# PCB-DISP128x32.net
KiCad netlist of a schematic drawn in EAGLE
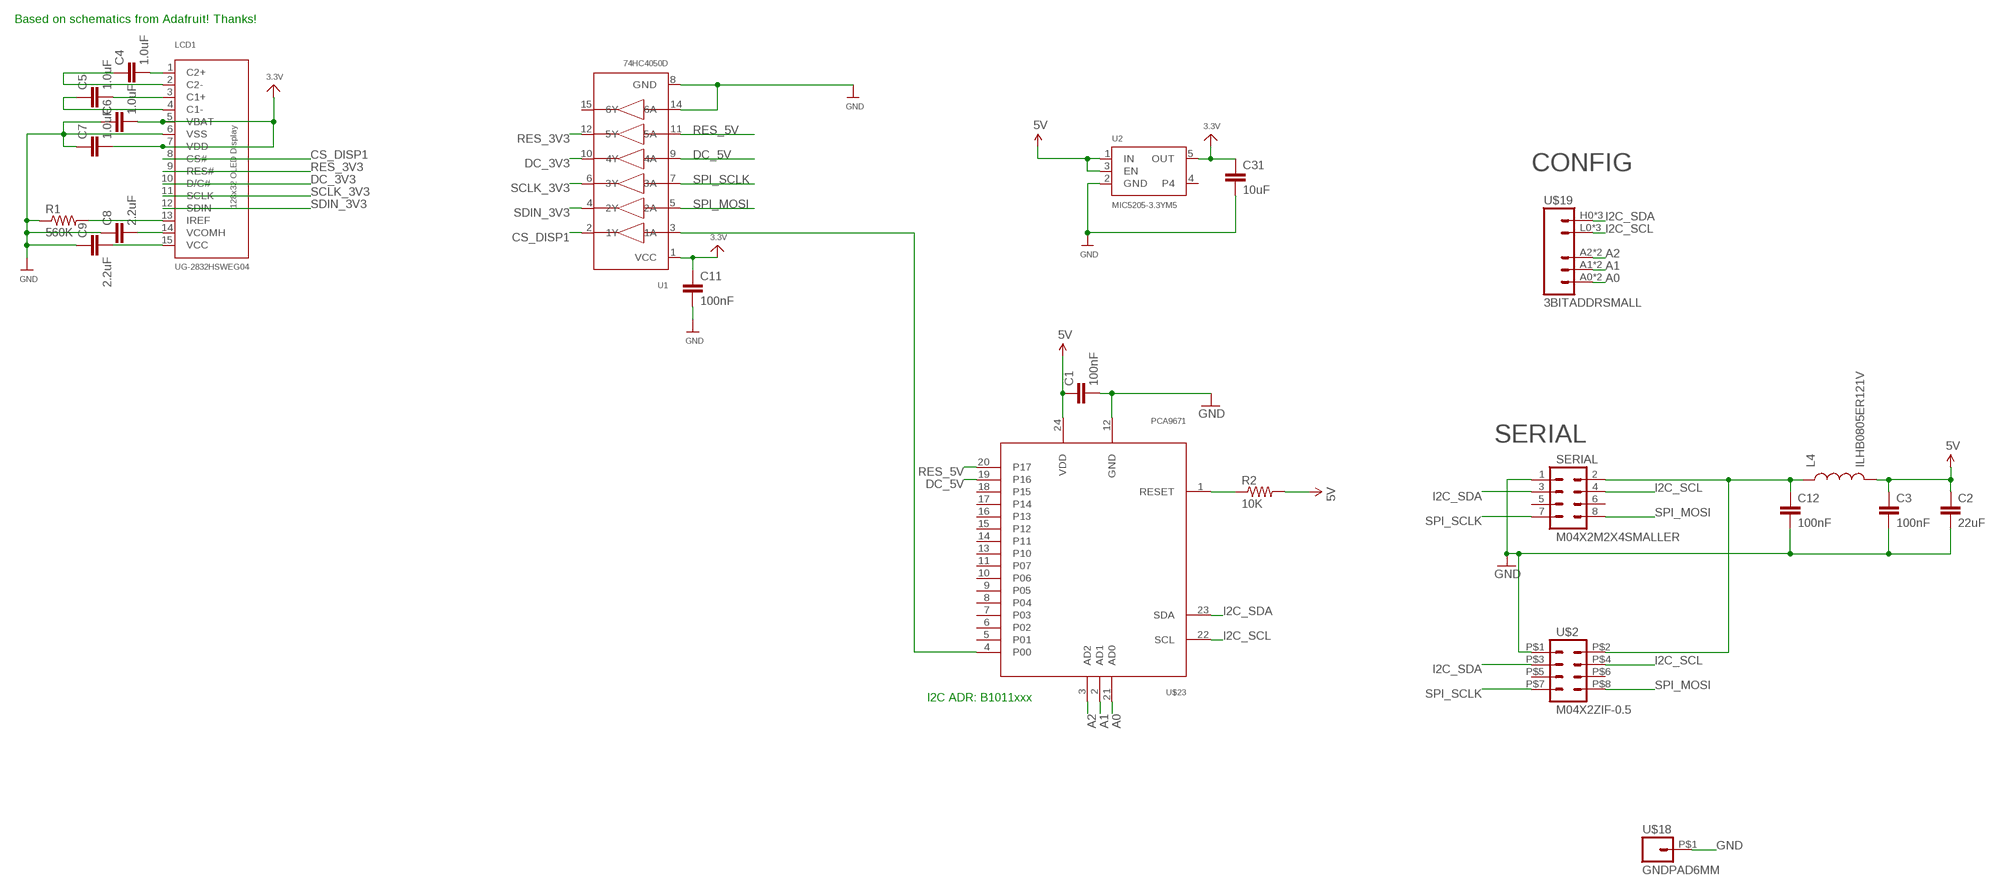
[diagram p0: schematic, sheet 1]

(export (version "E")
  (design (tool "Eeschema 10.0.6"))
  (components
    (comp (ref "C1")
      (value "100nF")
      (footprint "eagle-import:0603-CAP")
      (libsource (lib "eagle-import") (part "CAP0603-CAP"))
    )
    (comp (ref "C2")
      (value "22uF")
      (footprint "eagle-import:0805")
      (libsource (lib "eagle-import") (part "CAP0805"))
    )
    (comp (ref "C3")
      (value "100nF")
      (footprint "eagle-import:0603-CAP")
      (libsource (lib "eagle-import") (part "CAP0603-CAP"))
    )
    (comp (ref "C4")
      (value "1.0uF")
      (footprint "eagle-import:0603-CAP")
      (libsource (lib "eagle-import") (part "CAP0603-CAP"))
    )
    (comp (ref "C5")
      (value "1.0uF")
      (footprint "eagle-import:0603-CAP")
      (libsource (lib "eagle-import") (part "CAP0603-CAP"))
    )
    (comp (ref "C6")
      (value "1.0uF")
      (footprint "eagle-import:0603-CAP")
      (libsource (lib "eagle-import") (part "CAP0603-CAP"))
    )
    (comp (ref "C7")
      (value "1.0uF")
      (footprint "eagle-import:0603-CAP")
      (libsource (lib "eagle-import") (part "CAP0603-CAP"))
    )
    (comp (ref "C8")
      (value "2.2uF")
      (footprint "eagle-import:0603-CAP")
      (libsource (lib "eagle-import") (part "CAP0603-CAP"))
    )
    (comp (ref "C9")
      (value "2.2uF")
      (footprint "eagle-import:0603-CAP")
      (libsource (lib "eagle-import") (part "CAP0603-CAP"))
    )
    (comp (ref "C11")
      (value "100nF")
      (footprint "eagle-import:0603-CAP")
      (libsource (lib "eagle-import") (part "CAP0603-CAP"))
    )
    (comp (ref "C12")
      (value "100nF")
      (footprint "eagle-import:0603-CAP")
      (libsource (lib "eagle-import") (part "CAP0603-CAP"))
    )
    (comp (ref "C31")
      (value "10uF")
      (footprint "eagle-import:0805")
      (libsource (lib "eagle-import") (part "CAP0805"))
    )
    (comp (ref "L4")
      (value "ILHB0805ER121V")
      (footprint "eagle-import:0805")
      (libsource (lib "eagle-import") (part "INDUCTOR0805"))
    )
    (comp (ref "LCD1")
      (value "UG-2832HSWEG04")
      (footprint "eagle-import:UG-2832HSWEG04_WRAPAROUND")
      (libsource (lib "eagle-import") (part "OLED_UG-2832HSWEG04WRAPAROUND"))
    )
    (comp (ref "R1")
      (value "560K")
      (footprint "eagle-import:0603-RES")
      (libsource (lib "eagle-import") (part "RESISTOR0603-RES"))
    )
    (comp (ref "R2")
      (value "10K")
      (footprint "eagle-import:0603-RES")
      (libsource (lib "eagle-import") (part "RESISTOR0603-RES"))
    )
    (comp (ref "SERIAL")
      (value "M04X2M2X4SMALLER")
      (footprint "eagle-import:M2X4SMALLER")
      (libsource (lib "eagle-import") (part "M04X2M2X4SMALLER"))
    )
    (comp (ref "U$2")
      (value "M04X2ZIF-0.5")
      (footprint "eagle-import:ZIP-8-0.5")
      (libsource (lib "eagle-import") (part "M04X2ZIF-0.5"))
    )
    (comp (ref "U$18")
      (value "GNDPAD6MM")
      (footprint "eagle-import:3.2MMPAD6MM")
      (libsource (lib "eagle-import") (part "GNDPAD6MM"))
    )
    (comp (ref "U$19")
      (value "3BITADDRSMALL")
      (footprint "eagle-import:3BITADDR_SMALL")
      (libsource (lib "eagle-import") (part "3BITADDRSMALL"))
    )
    (comp (ref "U$23")
      (value "PCA9671")
      (footprint "eagle-import:TSSOP24")
      (libsource (lib "eagle-import") (part "PCA9671"))
    )
    (comp (ref "U1")
      (value "74HC4050D")
      (footprint "eagle-import:TSSOP16")
      (libsource (lib "eagle-import") (part "74HC4050DTSSOP16"))
    )
    (comp (ref "U2")
      (value "MIC5205-3.3YM5")
      (footprint "eagle-import:SOT23-5")
      (libsource (lib "eagle-import") (part "VREG_SOT23-5"))
    )
  )
  (nets
    (net (code "1") (name "3.3V") (class "Default")
      (node (ref "C11") (pin "1") (pinfunction "1_1") (pintype "passive"))
      (node (ref "C31") (pin "1") (pinfunction "1_1") (pintype "passive"))
      (node (ref "C6") (pin "2") (pinfunction "2_2") (pintype "passive"))
      (node (ref "C7") (pin "2") (pinfunction "2_2") (pintype "passive"))
      (node (ref "LCD1") (pin "5") (pinfunction "VBAT_5") (pintype "bidirectional"))
      (node (ref "LCD1") (pin "7") (pinfunction "VDD_7") (pintype "bidirectional"))
      (node (ref "U1") (pin "1") (pinfunction "VCC_1") (pintype "bidirectional"))
      (node (ref "U2") (pin "5") (pinfunction "OUT_5") (pintype "bidirectional"))
    )
    (net (code "2") (name "5V") (class "Default")
      (node (ref "C1") (pin "1") (pinfunction "1_1") (pintype "passive"))
      (node (ref "C2") (pin "1") (pinfunction "1_1") (pintype "passive"))
      (node (ref "C3") (pin "1") (pinfunction "1_1") (pintype "passive"))
      (node (ref "L4") (pin "2") (pinfunction "2_2") (pintype "passive"))
      (node (ref "R2") (pin "2") (pinfunction "2_2") (pintype "passive"))
      (node (ref "U$23") (pin "24") (pinfunction "VDD_24") (pintype "power_in"))
      (node (ref "U2") (pin "1") (pinfunction "IN_1") (pintype "bidirectional"))
      (node (ref "U2") (pin "3") (pinfunction "EN_3") (pintype "bidirectional"))
    )
    (net (code "3") (name "A0") (class "Default")
      (node (ref "U$19") (pin "A0") (pinfunction "A0_A0") (pintype "passive"))
      (node (ref "U$19") (pin "AS0") (pinfunction "A0_AS0") (pintype "passive"))
      (node (ref "U$23") (pin "21") (pinfunction "AD0_21") (pintype "input"))
    )
    (net (code "4") (name "A1") (class "Default")
      (node (ref "U$19") (pin "A1") (pinfunction "A1_A1") (pintype "passive"))
      (node (ref "U$19") (pin "AS1") (pinfunction "A1_AS1") (pintype "passive"))
      (node (ref "U$23") (pin "2") (pinfunction "AD1_2") (pintype "input"))
    )
    (net (code "5") (name "A2") (class "Default")
      (node (ref "U$19") (pin "A2") (pinfunction "A2_A2") (pintype "passive"))
      (node (ref "U$19") (pin "AS2") (pinfunction "A2_AS2") (pintype "passive"))
      (node (ref "U$23") (pin "3") (pinfunction "AD2_3") (pintype "input"))
    )
    (net (code "6") (name "CS_DISP1") (class "Default")
      (node (ref "LCD1") (pin "8") (pinfunction "CS#_8") (pintype "bidirectional"))
      (node (ref "U1") (pin "2") (pinfunction "1Y_2") (pintype "bidirectional"))
    )
    (net (code "7") (name "DC_3V3") (class "Default")
      (node (ref "LCD1") (pin "10") (pinfunction "D/C#_10") (pintype "bidirectional"))
      (node (ref "U1") (pin "10") (pinfunction "4Y_10") (pintype "bidirectional"))
    )
    (net (code "8") (name "DC_5V") (class "Default")
      (node (ref "U$23") (pin "19") (pinfunction "P16_19") (pintype "output"))
      (node (ref "U1") (pin "9") (pinfunction "4A_9") (pintype "bidirectional"))
    )
    (net (code "9") (name "GND") (class "Default")
      (node (ref "C1") (pin "2") (pinfunction "2_2") (pintype "passive"))
      (node (ref "C11") (pin "2") (pinfunction "2_2") (pintype "passive"))
      (node (ref "C12") (pin "2") (pinfunction "2_2") (pintype "passive"))
      (node (ref "C2") (pin "2") (pinfunction "2_2") (pintype "passive"))
      (node (ref "C3") (pin "2") (pinfunction "2_2") (pintype "passive"))
      (node (ref "C31") (pin "2") (pinfunction "2_2") (pintype "passive"))
      (node (ref "C6") (pin "1") (pinfunction "1_1") (pintype "passive"))
      (node (ref "C7") (pin "1") (pinfunction "1_1") (pintype "passive"))
      (node (ref "C8") (pin "1") (pinfunction "1_1") (pintype "passive"))
      (node (ref "C9") (pin "1") (pinfunction "1_1") (pintype "passive"))
      (node (ref "LCD1") (pin "6") (pinfunction "VSS_6") (pintype "bidirectional"))
      (node (ref "R1") (pin "1") (pinfunction "1_1") (pintype "passive"))
      (node (ref "SERIAL") (pin "1") (pinfunction "1_1") (pintype "passive"))
      (node (ref "U$18") (pin "P$1") (pinfunction "1_P$1") (pintype "passive"))
      (node (ref "U$2") (pin "P$1") (pinfunction "1_P$1") (pintype "passive"))
      (node (ref "U$23") (pin "12") (pinfunction "GND_12") (pintype "power_in"))
      (node (ref "U1") (pin "14") (pinfunction "6A_14") (pintype "bidirectional"))
      (node (ref "U1") (pin "8") (pinfunction "GND_8") (pintype "bidirectional"))
      (node (ref "U2") (pin "2") (pinfunction "GND_2") (pintype "bidirectional"))
    )
    (net (code "10") (name "I2C_SCL") (class "Default")
      (node (ref "SERIAL") (pin "4") (pinfunction "4_4") (pintype "passive"))
      (node (ref "U$19") (pin "L0") (pinfunction "GND_L0") (pintype "passive"))
      (node (ref "U$19") (pin "L1") (pinfunction "GND_L1") (pintype "passive"))
      (node (ref "U$19") (pin "L2") (pinfunction "GND_L2") (pintype "passive"))
      (node (ref "U$2") (pin "P$4") (pinfunction "4_P$4") (pintype "passive"))
      (node (ref "U$23") (pin "22") (pinfunction "SCL_22") (pintype "input"))
    )
    (net (code "11") (name "I2C_SDA") (class "Default")
      (node (ref "SERIAL") (pin "3") (pinfunction "3_3") (pintype "passive"))
      (node (ref "U$19") (pin "H0") (pinfunction "VCC_H0") (pintype "passive"))
      (node (ref "U$19") (pin "H1") (pinfunction "VCC_H1") (pintype "passive"))
      (node (ref "U$19") (pin "H2") (pinfunction "VCC_H2") (pintype "passive"))
      (node (ref "U$2") (pin "P$3") (pinfunction "3_P$3") (pintype "passive"))
      (node (ref "U$23") (pin "23") (pinfunction "SDA_23") (pintype "input"))
    )
    (net (code "12") (name "Net-(LCD1-C1+)") (class "Default")
      (node (ref "C5") (pin "2") (pinfunction "2_2") (pintype "passive"))
      (node (ref "LCD1") (pin "3") (pinfunction "C1+_3") (pintype "bidirectional"))
    )
    (net (code "13") (name "Net-(LCD1-C1-)") (class "Default")
      (node (ref "C5") (pin "1") (pinfunction "1_1") (pintype "passive"))
      (node (ref "LCD1") (pin "4") (pinfunction "C1-_4") (pintype "bidirectional"))
    )
    (net (code "14") (name "Net-(LCD1-C2+)") (class "Default")
      (node (ref "C4") (pin "2") (pinfunction "2_2") (pintype "passive"))
      (node (ref "LCD1") (pin "1") (pinfunction "C2+_1") (pintype "bidirectional"))
    )
    (net (code "15") (name "Net-(LCD1-C2-)") (class "Default")
      (node (ref "C4") (pin "1") (pinfunction "1_1") (pintype "passive"))
      (node (ref "LCD1") (pin "2") (pinfunction "C2-_2") (pintype "bidirectional"))
    )
    (net (code "16") (name "Net-(LCD1-IREF)") (class "Default")
      (node (ref "LCD1") (pin "13") (pinfunction "IREF_13") (pintype "bidirectional"))
      (node (ref "R1") (pin "2") (pinfunction "2_2") (pintype "passive"))
    )
    (net (code "17") (name "Net-(LCD1-VCC)") (class "Default")
      (node (ref "C9") (pin "2") (pinfunction "2_2") (pintype "passive"))
      (node (ref "LCD1") (pin "15") (pinfunction "VCC_15") (pintype "bidirectional"))
    )
    (net (code "18") (name "Net-(LCD1-VCOMH)") (class "Default")
      (node (ref "C8") (pin "2") (pinfunction "2_2") (pintype "passive"))
      (node (ref "LCD1") (pin "14") (pinfunction "VCOMH_14") (pintype "bidirectional"))
    )
    (net (code "19") (name "Net-(U$2-2)") (class "Default")
      (node (ref "C12") (pin "1") (pinfunction "1_1") (pintype "passive"))
      (node (ref "L4") (pin "1") (pinfunction "1_1") (pintype "passive"))
      (node (ref "SERIAL") (pin "2") (pinfunction "2_2") (pintype "passive"))
      (node (ref "U$2") (pin "P$2") (pinfunction "2_P$2") (pintype "passive"))
    )
    (net (code "20") (name "Net-(U$23-P00)") (class "Default")
      (node (ref "U$23") (pin "4") (pinfunction "P00_4") (pintype "output"))
      (node (ref "U1") (pin "3") (pinfunction "1A_3") (pintype "bidirectional"))
    )
    (net (code "21") (name "Net-(U$23-RESET)") (class "Default")
      (node (ref "R2") (pin "1") (pinfunction "1_1") (pintype "passive"))
      (node (ref "U$23") (pin "1") (pinfunction "RESET_1") (pintype "input"))
    )
    (net (code "22") (name "RES_3V3") (class "Default")
      (node (ref "LCD1") (pin "9") (pinfunction "RES#_9") (pintype "bidirectional"))
      (node (ref "U1") (pin "12") (pinfunction "5Y_12") (pintype "bidirectional"))
    )
    (net (code "23") (name "RES_5V") (class "Default")
      (node (ref "U$23") (pin "20") (pinfunction "P17_20") (pintype "output"))
      (node (ref "U1") (pin "11") (pinfunction "5A_11") (pintype "bidirectional"))
    )
    (net (code "24") (name "SCLK_3V3") (class "Default")
      (node (ref "LCD1") (pin "11") (pinfunction "SCLK_11") (pintype "bidirectional"))
      (node (ref "U1") (pin "6") (pinfunction "3Y_6") (pintype "bidirectional"))
    )
    (net (code "25") (name "SDIN_3V3") (class "Default")
      (node (ref "LCD1") (pin "12") (pinfunction "SDIN_12") (pintype "bidirectional"))
      (node (ref "U1") (pin "4") (pinfunction "2Y_4") (pintype "bidirectional"))
    )
    (net (code "26") (name "SPI_MOSI") (class "Default")
      (node (ref "SERIAL") (pin "8") (pinfunction "8_8") (pintype "passive"))
      (node (ref "U$2") (pin "P$8") (pinfunction "8_P$8") (pintype "passive"))
      (node (ref "U1") (pin "5") (pinfunction "2A_5") (pintype "bidirectional"))
    )
    (net (code "27") (name "SPI_SCLK") (class "Default")
      (node (ref "SERIAL") (pin "7") (pinfunction "7_7") (pintype "passive"))
      (node (ref "U$2") (pin "P$7") (pinfunction "7_P$7") (pintype "passive"))
      (node (ref "U1") (pin "7") (pinfunction "3A_7") (pintype "bidirectional"))
    )
    (net (code "28") (name "unconnected-(SERIAL-Pad5)") (class "Default")
      (node (ref "SERIAL") (pin "5") (pinfunction "5_5") (pintype "passive"))
    )
    (net (code "29") (name "unconnected-(SERIAL-Pad6)") (class "Default")
      (node (ref "SERIAL") (pin "6") (pinfunction "6_6") (pintype "passive"))
    )
    (net (code "30") (name "unconnected-(U$2-5-PadP$5)") (class "Default")
      (node (ref "U$2") (pin "P$5") (pinfunction "5_P$5") (pintype "passive"))
    )
    (net (code "31") (name "unconnected-(U$2-6-PadP$6)") (class "Default")
      (node (ref "U$2") (pin "P$6") (pinfunction "6_P$6") (pintype "passive"))
    )
    (net (code "32") (name "unconnected-(U$23-P01-Pad5)") (class "Default")
      (node (ref "U$23") (pin "5") (pinfunction "P01_5") (pintype "output"))
    )
    (net (code "33") (name "unconnected-(U$23-P02-Pad6)") (class "Default")
      (node (ref "U$23") (pin "6") (pinfunction "P02_6") (pintype "output"))
    )
    (net (code "34") (name "unconnected-(U$23-P03-Pad7)") (class "Default")
      (node (ref "U$23") (pin "7") (pinfunction "P03_7") (pintype "output"))
    )
    (net (code "35") (name "unconnected-(U$23-P04-Pad8)") (class "Default")
      (node (ref "U$23") (pin "8") (pinfunction "P04_8") (pintype "output"))
    )
    (net (code "36") (name "unconnected-(U$23-P05-Pad9)") (class "Default")
      (node (ref "U$23") (pin "9") (pinfunction "P05_9") (pintype "output"))
    )
    (net (code "37") (name "unconnected-(U$23-P06-Pad10)") (class "Default")
      (node (ref "U$23") (pin "10") (pinfunction "P06_10") (pintype "output"))
    )
    (net (code "38") (name "unconnected-(U$23-P07-Pad11)") (class "Default")
      (node (ref "U$23") (pin "11") (pinfunction "P07_11") (pintype "output"))
    )
    (net (code "39") (name "unconnected-(U$23-P10-Pad13)") (class "Default")
      (node (ref "U$23") (pin "13") (pinfunction "P10_13") (pintype "output"))
    )
    (net (code "40") (name "unconnected-(U$23-P11-Pad14)") (class "Default")
      (node (ref "U$23") (pin "14") (pinfunction "P11_14") (pintype "output"))
    )
    (net (code "41") (name "unconnected-(U$23-P12-Pad15)") (class "Default")
      (node (ref "U$23") (pin "15") (pinfunction "P12_15") (pintype "output"))
    )
    (net (code "42") (name "unconnected-(U$23-P13-Pad16)") (class "Default")
      (node (ref "U$23") (pin "16") (pinfunction "P13_16") (pintype "output"))
    )
    (net (code "43") (name "unconnected-(U$23-P14-Pad17)") (class "Default")
      (node (ref "U$23") (pin "17") (pinfunction "P14_17") (pintype "output"))
    )
    (net (code "44") (name "unconnected-(U$23-P15-Pad18)") (class "Default")
      (node (ref "U$23") (pin "18") (pinfunction "P15_18") (pintype "output"))
    )
    (net (code "45") (name "unconnected-(U1-6Y-Pad15)") (class "Default")
      (node (ref "U1") (pin "15") (pinfunction "6Y_15") (pintype "bidirectional"))
    )
    (net (code "46") (name "unconnected-(U2-P4-Pad4)") (class "Default")
      (node (ref "U2") (pin "4") (pinfunction "P4_4") (pintype "bidirectional"))
    )
  )
)
